# Knot_Thing_nRF.net
KiCad netlist of a schematic drawn in Altium Designer
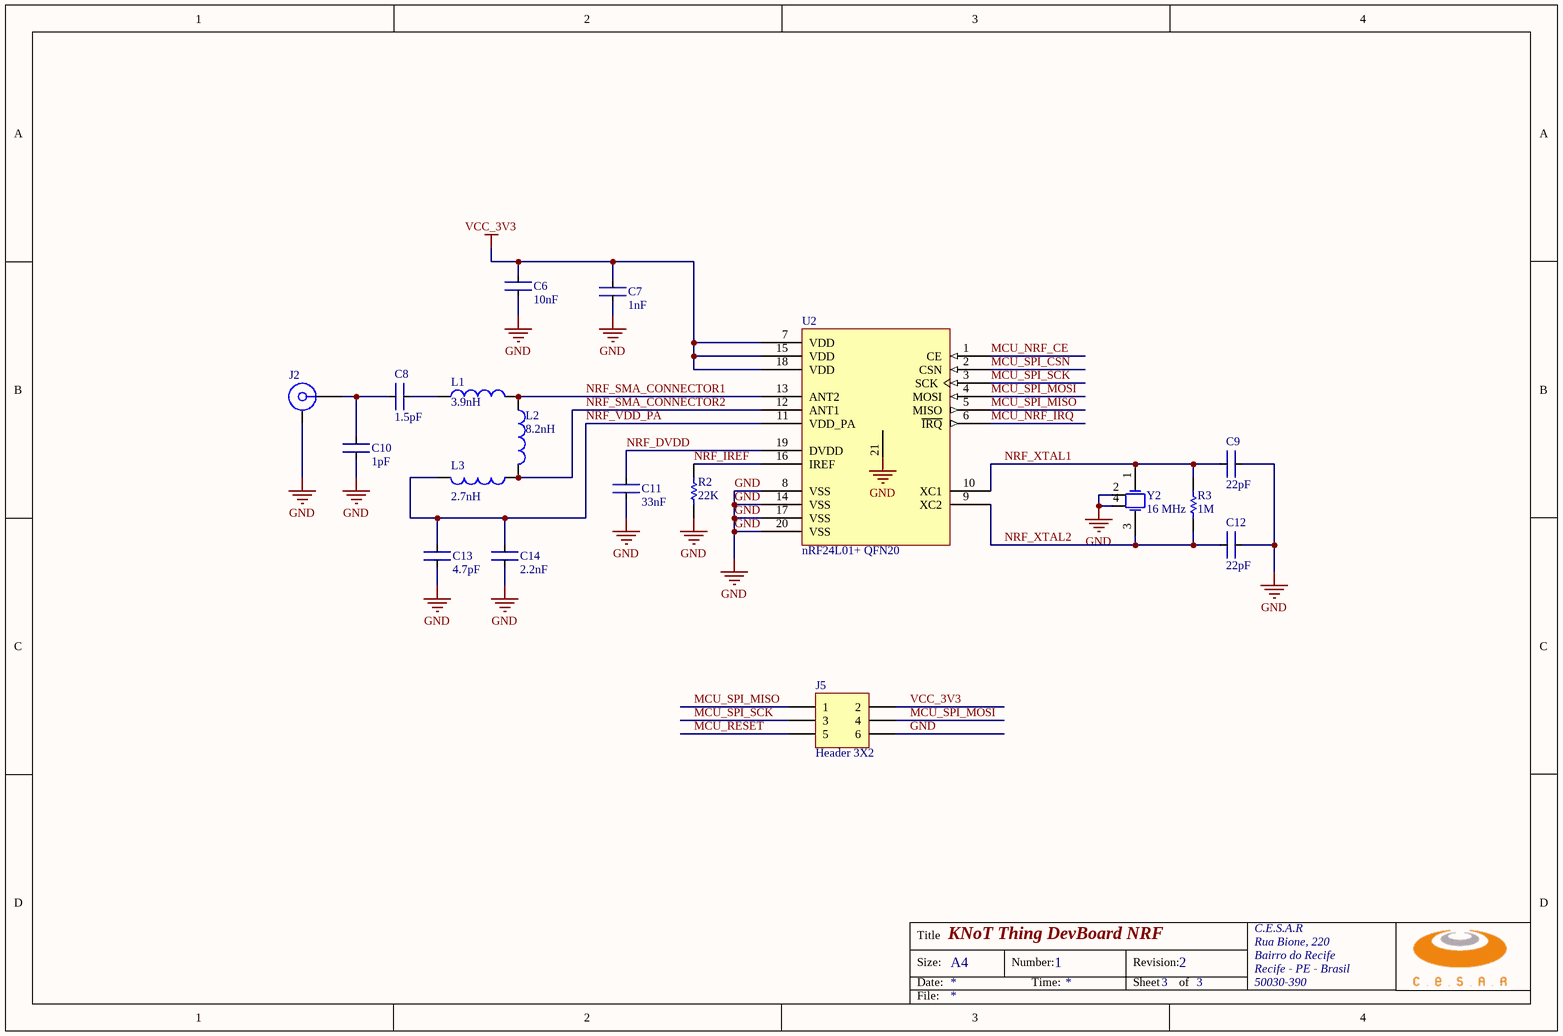
[diagram p0: Knot_Thing_nRF.SchDoc]

(export (version "E")
  (design (tool "Eeschema 10.0.6"))
  (components
    (comp (ref "C6")
      (value "10nF")
      (footprint "CAPC1005L")
      (description "Chip Capacitor 0402 (1005 metric)")
      (fields (field (name "Comment") "Cap_0402"))
      (libsource (lib "KNoT_Thing") (part "Capacitor_0402"))
    )
    (comp (ref "C7")
      (value "1nF")
      (footprint "CAPC1005L")
      (description "Chip Capacitor 0402 (1005 metric)")
      (fields (field (name "Comment") "Cap_0402"))
      (libsource (lib "KNoT_Thing") (part "Capacitor_0402"))
    )
    (comp (ref "C8")
      (value "1.5pF")
      (footprint "CAPC1005L")
      (description "Chip Capacitor 0402 (1005 metric)")
      (fields (field (name "Comment") "Cap_0402"))
      (libsource (lib "KNoT_Thing") (part "Capacitor_0402"))
    )
    (comp (ref "C9")
      (value "22pF")
      (footprint "CAPC1005L")
      (description "Chip Capacitor 0402 (1005 metric)")
      (fields (field (name "Comment") "Cap_0402"))
      (libsource (lib "KNoT_Thing") (part "Capacitor_0402"))
    )
    (comp (ref "C10")
      (value "1pF")
      (footprint "CAPC1005L")
      (description "Chip Capacitor 0402 (1005 metric)")
      (fields (field (name "Comment") "Cap_0402"))
      (libsource (lib "KNoT_Thing") (part "Capacitor_0402"))
    )
    (comp (ref "C11")
      (value "33nF")
      (footprint "CAPC1005L")
      (description "Chip Capacitor 0402 (1005 metric)")
      (fields (field (name "Comment") "Cap_0402"))
      (libsource (lib "KNoT_Thing") (part "Capacitor_0402"))
    )
    (comp (ref "C12")
      (value "22pF")
      (footprint "CAPC1005L")
      (description "Chip Capacitor 0402 (1005 metric)")
      (fields (field (name "Comment") "Cap_0402"))
      (libsource (lib "KNoT_Thing") (part "Capacitor_0402"))
    )
    (comp (ref "C13")
      (value "4.7pF")
      (footprint "CAPC1005L")
      (description "Chip Capacitor 0402 (1005 metric)")
      (fields (field (name "Comment") "Cap_0402"))
      (libsource (lib "KNoT_Thing") (part "Capacitor_0402"))
    )
    (comp (ref "C14")
      (value "2.2nF")
      (footprint "CAPC1005L")
      (description "Chip Capacitor 0402 (1005 metric)")
      (fields (field (name "Comment") "Cap_0402"))
      (libsource (lib "KNoT_Thing") (part "Capacitor_0402"))
    )
    (comp (ref "J2")
      (value "32K249-400L5")
      (footprint "ROS-32K249-400L5_V")
      (description "SMA Right Angle Jack, Up to 18 GHz, -65 to 165 degC")
      (libsource (lib "KNoT_Thing") (part "32K249-400L5"))
    )
    (comp (ref "J5")
      (value "Header 3X2")
      (footprint "HDR2X3")
      (description "Header, 3-Pin, Dual row")
      (fields (field (name "PUBLISHER") "Altium Limited"))
      (libsource (lib "KNoT_Thing") (part "Header 3X2"))
    )
    (comp (ref "L1")
      (value "Inductor0402")
      (footprint "CAPC1005L")
      (description "Inductor 27nH")
      (fields (field (name "ALTIUM_UNNAMED_1") "3.9nH"))
      (libsource (lib "KNoT_Thing") (part "Inductor0402"))
    )
    (comp (ref "L2")
      (value "Inductor0402")
      (footprint "CAPC1005L")
      (description "Inductor 27nH")
      (fields (field (name "ALTIUM_UNNAMED_1") "8.2nH"))
      (libsource (lib "KNoT_Thing") (part "Inductor0402"))
    )
    (comp (ref "L3")
      (value "Inductor0402")
      (footprint "CAPC1005L")
      (description "Inductor 27nH")
      (fields (field (name "ALTIUM_UNNAMED_1") "2.7nH"))
      (libsource (lib "KNoT_Thing") (part "Inductor0402"))
    )
    (comp (ref "R2")
      (value "22K")
      (footprint "CAPC1005L")
      (fields (field (name "Comment") "RES_0402"))
      (libsource (lib "KNoT_Thing") (part "RES_0402"))
    )
    (comp (ref "R3")
      (value "1M")
      (footprint "CAPC1005L")
      (fields (field (name "Comment") "RES_0402"))
      (libsource (lib "KNoT_Thing") (part "RES_0402"))
    )
    (comp (ref "U2")
      (value "nRF24L01+ QFN20")
      (footprint "QFN20")
      (description "IC RF TxRx Only General ISM > 1GHZ 2.4GHz")
      (libsource (lib "KNoT_Thing") (part "nRF24L01+"))
    )
    (comp (ref "Y2")
      (value "16 MHz")
      (footprint "SPK-16M-5032")
      (description "Crystal FOXSLF/080-20")
      (libsource (lib "KNoT_Thing") (part "XTAL_SMD"))
    )
  )
  (nets
    (net (code "1") (name "/MCU_NRF_CE") (class "Default")
      (node (ref "U2") (pin "1") (pinfunction "CE_1") (pintype "input"))
    )
    (net (code "2") (name "/MCU_NRF_IRQ") (class "Default")
      (node (ref "U2") (pin "6") (pinfunction "~{IRQ}_6") (pintype "output"))
    )
    (net (code "3") (name "/MCU_RESET") (class "Default")
      (node (ref "J5") (pin "5") (pinfunction "5_5") (pintype "passive"))
    )
    (net (code "4") (name "/MCU_SPI_CSN") (class "Default")
      (node (ref "U2") (pin "2") (pinfunction "CSN_2") (pintype "input"))
    )
    (net (code "5") (name "/MCU_SPI_MISO") (class "Default")
      (node (ref "J5") (pin "1") (pinfunction "1_1") (pintype "passive"))
      (node (ref "U2") (pin "5") (pinfunction "MISO_5") (pintype "output"))
    )
    (net (code "6") (name "/MCU_SPI_MOSI") (class "Default")
      (node (ref "J5") (pin "4") (pinfunction "4_4") (pintype "passive"))
      (node (ref "U2") (pin "4") (pinfunction "MOSI_4") (pintype "input"))
    )
    (net (code "7") (name "/MCU_SPI_SCK") (class "Default")
      (node (ref "J5") (pin "3") (pinfunction "3_3") (pintype "passive"))
      (node (ref "U2") (pin "3") (pinfunction "SCK_3") (pintype "input"))
    )
    (net (code "8") (name "/NRF_DVDD") (class "Default")
      (node (ref "C11") (pin "2") (pinfunction "0_2") (pintype "passive"))
      (node (ref "U2") (pin "19") (pinfunction "DVDD_19") (pintype "power_in"))
    )
    (net (code "9") (name "/NRF_IREF") (class "Default")
      (node (ref "R2") (pin "2") (pinfunction "2_2") (pintype "passive"))
      (node (ref "U2") (pin "16") (pinfunction "IREF_16") (pintype "power_in"))
    )
    (net (code "10") (name "/NRF_SMA_CONNECTOR1") (class "Default")
      (node (ref "L1") (pin "2") (pinfunction "2_2") (pintype "passive"))
      (node (ref "L2") (pin "1") (pinfunction "1_1") (pintype "passive"))
      (node (ref "U2") (pin "13") (pinfunction "ANT2_13") (pintype "passive"))
    )
    (net (code "11") (name "/NRF_SMA_CONNECTOR2") (class "Default")
      (node (ref "L2") (pin "2") (pinfunction "2_2") (pintype "passive"))
      (node (ref "L3") (pin "1") (pinfunction "1_1") (pintype "passive"))
      (node (ref "U2") (pin "12") (pinfunction "ANT1_12") (pintype "passive"))
    )
    (net (code "12") (name "/NRF_VDD_PA") (class "Default")
      (node (ref "C13") (pin "2") (pinfunction "0_2") (pintype "passive"))
      (node (ref "C14") (pin "2") (pinfunction "0_2") (pintype "passive"))
      (node (ref "L3") (pin "2") (pinfunction "2_2") (pintype "passive"))
      (node (ref "U2") (pin "11") (pinfunction "VDD_PA_11") (pintype "passive"))
    )
    (net (code "13") (name "/NRF_XTAL1") (class "Default")
      (node (ref "C9") (pin "2") (pinfunction "0_2") (pintype "passive"))
      (node (ref "R3") (pin "1") (pinfunction "1_1") (pintype "passive"))
      (node (ref "U2") (pin "10") (pinfunction "XC1_10") (pintype "passive"))
      (node (ref "Y2") (pin "1") (pinfunction "OSC1_1") (pintype "passive"))
    )
    (net (code "14") (name "/NRF_XTAL2") (class "Default")
      (node (ref "C12") (pin "1") (pinfunction "1_1") (pintype "passive"))
      (node (ref "R3") (pin "2") (pinfunction "2_2") (pintype "passive"))
      (node (ref "U2") (pin "9") (pinfunction "XC2_9") (pintype "passive"))
      (node (ref "Y2") (pin "3") (pinfunction "OSC2_3") (pintype "passive"))
    )
    (net (code "15") (name "GND") (class "Default")
      (node (ref "C10") (pin "1") (pinfunction "1_1") (pintype "passive"))
      (node (ref "C11") (pin "1") (pinfunction "1_1") (pintype "passive"))
      (node (ref "C12") (pin "2") (pinfunction "0_2") (pintype "passive"))
      (node (ref "C13") (pin "1") (pinfunction "1_1") (pintype "passive"))
      (node (ref "C14") (pin "1") (pinfunction "1_1") (pintype "passive"))
      (node (ref "C6") (pin "1") (pinfunction "1_1") (pintype "passive"))
      (node (ref "C7") (pin "1") (pinfunction "1_1") (pintype "passive"))
      (node (ref "C9") (pin "1") (pinfunction "1_1") (pintype "passive"))
      (node (ref "J2") (pin "MH") (pinfunction "MH_MH") (pintype "passive"))
      (node (ref "J5") (pin "6") (pinfunction "6_6") (pintype "passive"))
      (node (ref "R2") (pin "1") (pinfunction "1_1") (pintype "passive"))
      (node (ref "U2") (pin "14") (pinfunction "VSS_14") (pintype "power_in"))
      (node (ref "U2") (pin "17") (pinfunction "VSS_17") (pintype "power_in"))
      (node (ref "U2") (pin "20") (pinfunction "VSS_20") (pintype "power_in"))
      (node (ref "U2") (pin "21") (pinfunction "21_21") (pintype "power_in"))
      (node (ref "U2") (pin "8") (pinfunction "VSS_8") (pintype "power_in"))
      (node (ref "Y2") (pin "2") (pinfunction "2_2") (pintype "passive"))
      (node (ref "Y2") (pin "4") (pinfunction "4_4") (pintype "passive"))
    )
    (net (code "16") (name "Net-(C8-0)") (class "Default")
      (node (ref "C8") (pin "2") (pinfunction "0_2") (pintype "passive"))
      (node (ref "L1") (pin "1") (pinfunction "1_1") (pintype "passive"))
    )
    (net (code "17") (name "Net-(C10-0)") (class "Default")
      (node (ref "C10") (pin "2") (pinfunction "0_2") (pintype "passive"))
      (node (ref "C8") (pin "1") (pinfunction "1_1") (pintype "passive"))
      (node (ref "J2") (pin "1") (pinfunction "1_1") (pintype "passive"))
    )
    (net (code "18") (name "VCC_3V3") (class "Default")
      (node (ref "C6") (pin "2") (pinfunction "0_2") (pintype "passive"))
      (node (ref "C7") (pin "2") (pinfunction "0_2") (pintype "passive"))
      (node (ref "J5") (pin "2") (pinfunction "2_2") (pintype "passive"))
      (node (ref "U2") (pin "15") (pinfunction "VDD_15") (pintype "power_in"))
      (node (ref "U2") (pin "18") (pinfunction "VDD_18") (pintype "power_in"))
      (node (ref "U2") (pin "7") (pinfunction "VDD_7") (pintype "power_in"))
    )
  )
)
